# nes_mini.net
KiCad netlist of a schematic drawn in EAGLE
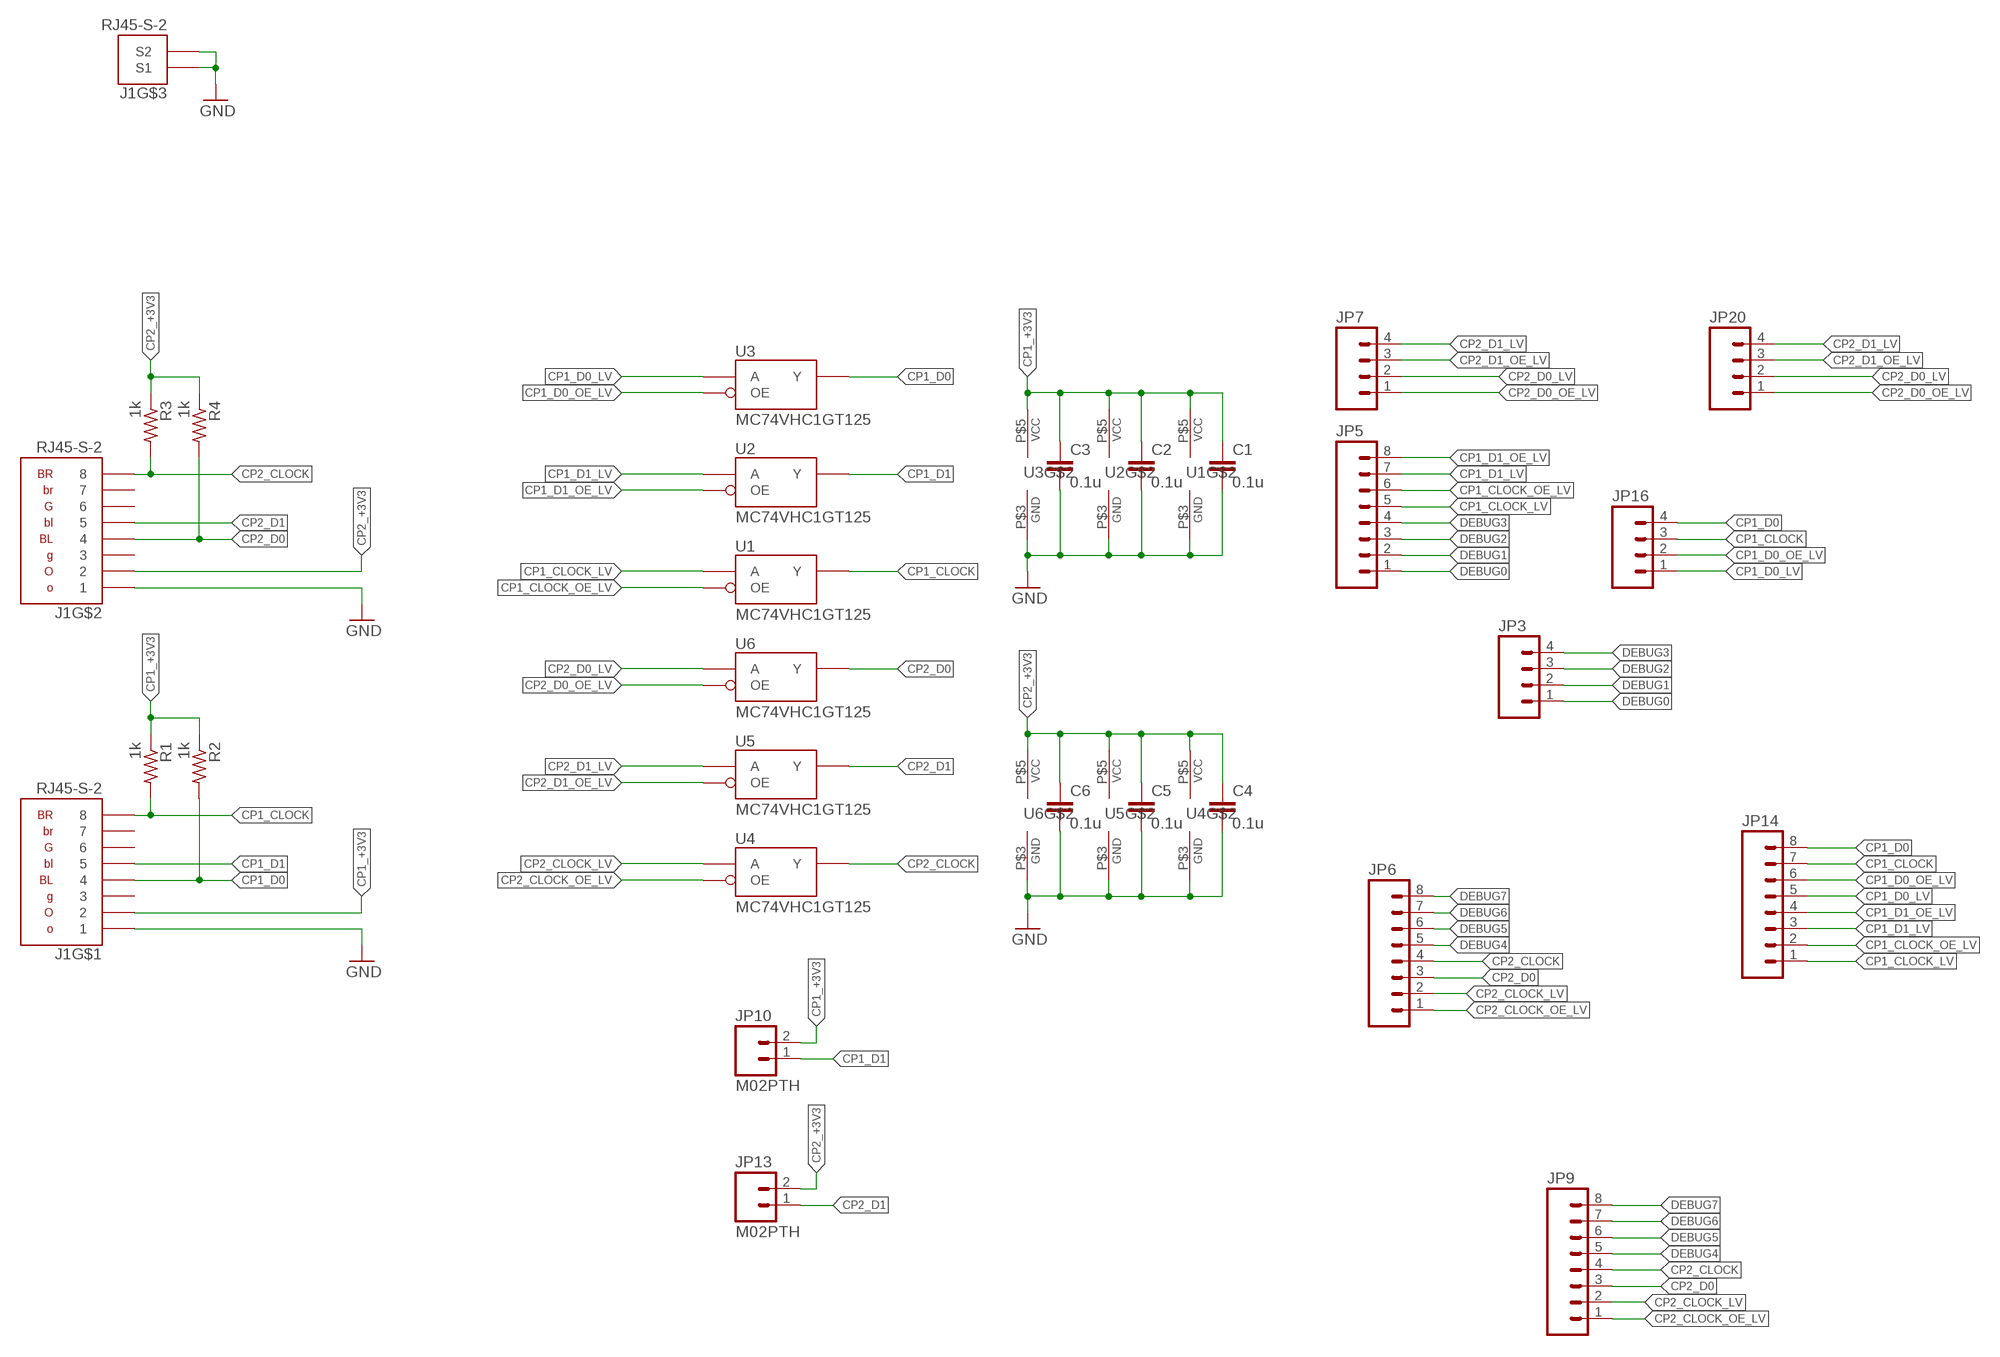
[diagram p0: schematic, sheet 1, part 1 of 2]
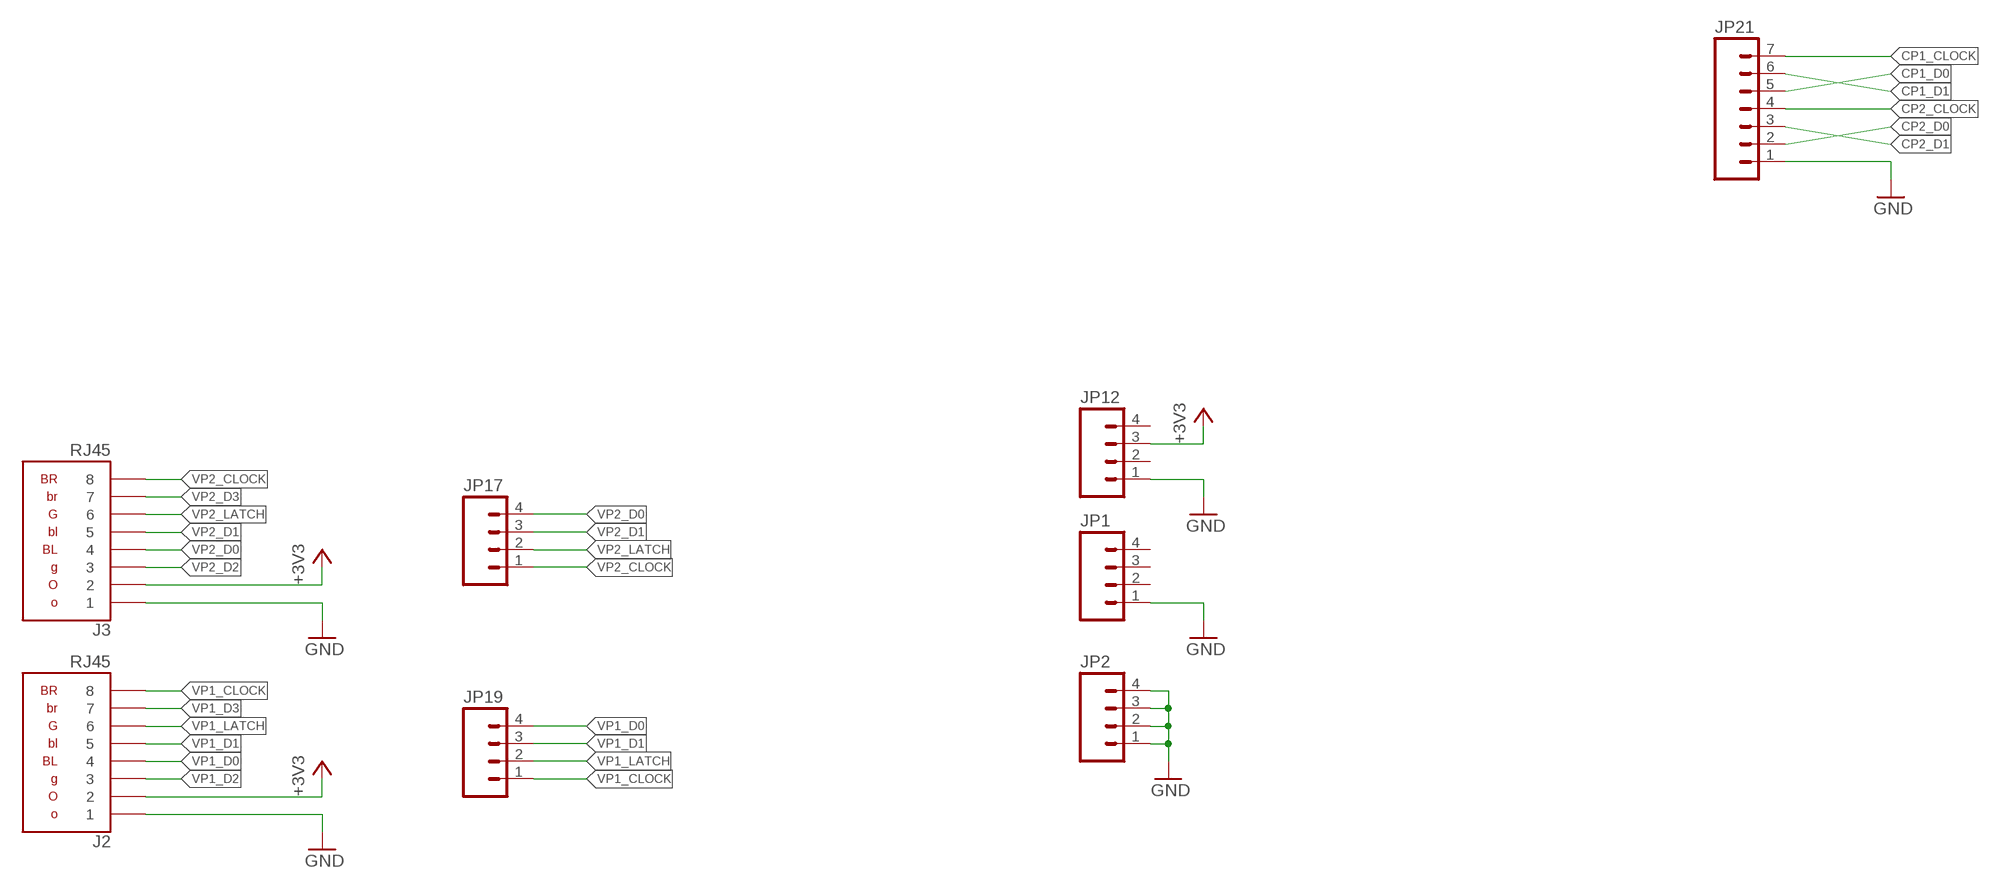
[diagram p1: schematic, sheet 1, part 2 of 2]

(export (version "E")
  (design (tool "Eeschema 10.0.6"))
  (components
    (comp (ref "C1")
      (value "0.1u")
      (footprint "eagle-import:C0603")
      (libsource (lib "eagle-import") (part "C-EUC0603"))
    )
    (comp (ref "C2")
      (value "0.1u")
      (footprint "eagle-import:C0603")
      (libsource (lib "eagle-import") (part "C-EUC0603"))
    )
    (comp (ref "C3")
      (value "0.1u")
      (footprint "eagle-import:C0603")
      (libsource (lib "eagle-import") (part "C-EUC0603"))
    )
    (comp (ref "C4")
      (value "0.1u")
      (footprint "eagle-import:C0603")
      (libsource (lib "eagle-import") (part "C-EUC0603"))
    )
    (comp (ref "C5")
      (value "0.1u")
      (footprint "eagle-import:C0603")
      (libsource (lib "eagle-import") (part "C-EUC0603"))
    )
    (comp (ref "C6")
      (value "0.1u")
      (footprint "eagle-import:C0603")
      (libsource (lib "eagle-import") (part "C-EUC0603"))
    )
    (comp (ref "J1")
      (value "RJ45-S-2")
      (footprint "eagle-import:RJ45-S-2")
      (libsource (lib "eagle-import") (part "RJ45-S-2"))
    )
    (comp (ref "J2")
      (value "RJ45")
      (footprint "eagle-import:RJ45")
      (libsource (lib "eagle-import") (part "RJ45"))
    )
    (comp (ref "J3")
      (value "RJ45")
      (footprint "eagle-import:RJ45")
      (libsource (lib "eagle-import") (part "RJ45"))
    )
    (comp (ref "JP1")
      (value "M04PTH")
      (footprint "eagle-import:1X04")
      (libsource (lib "eagle-import") (part "M04PTH"))
    )
    (comp (ref "JP2")
      (value "M04PTH")
      (footprint "eagle-import:1X04")
      (libsource (lib "eagle-import") (part "M04PTH"))
    )
    (comp (ref "JP3")
      (value "M04PTH")
      (footprint "eagle-import:1X04")
      (libsource (lib "eagle-import") (part "M04PTH"))
    )
    (comp (ref "JP5")
      (value "M081X08")
      (footprint "eagle-import:1X08")
      (libsource (lib "eagle-import") (part "M081X08"))
    )
    (comp (ref "JP6")
      (value "M081X08")
      (footprint "eagle-import:1X08")
      (libsource (lib "eagle-import") (part "M081X08"))
    )
    (comp (ref "JP7")
      (value "M04PTH")
      (footprint "eagle-import:1X04")
      (libsource (lib "eagle-import") (part "M04PTH"))
    )
    (comp (ref "JP9")
      (value "M081X08")
      (footprint "eagle-import:1X08")
      (libsource (lib "eagle-import") (part "M081X08"))
    )
    (comp (ref "JP10")
      (value "M02PTH")
      (footprint "eagle-import:1X02")
      (libsource (lib "eagle-import") (part "M02PTH"))
    )
    (comp (ref "JP12")
      (value "M04PTH")
      (footprint "eagle-import:1X04")
      (libsource (lib "eagle-import") (part "M04PTH"))
    )
    (comp (ref "JP13")
      (value "M02PTH")
      (footprint "eagle-import:1X02")
      (libsource (lib "eagle-import") (part "M02PTH"))
    )
    (comp (ref "JP14")
      (value "M081X08")
      (footprint "eagle-import:1X08")
      (libsource (lib "eagle-import") (part "M081X08"))
    )
    (comp (ref "JP16")
      (value "M04PTH")
      (footprint "eagle-import:1X04")
      (libsource (lib "eagle-import") (part "M04PTH"))
    )
    (comp (ref "JP17")
      (value "M04PTH")
      (footprint "eagle-import:1X04")
      (libsource (lib "eagle-import") (part "M04PTH"))
    )
    (comp (ref "JP19")
      (value "M04PTH")
      (footprint "eagle-import:1X04")
      (libsource (lib "eagle-import") (part "M04PTH"))
    )
    (comp (ref "JP20")
      (value "M04PTH")
      (footprint "eagle-import:1X04")
      (libsource (lib "eagle-import") (part "M04PTH"))
    )
    (comp (ref "JP21")
      (value "M07")
      (footprint "eagle-import:1X07")
      (libsource (lib "eagle-import") (part "M07"))
    )
    (comp (ref "R1")
      (value "1k")
      (footprint "eagle-import:0207_2V")
      (libsource (lib "eagle-import") (part "R-US_0207/2V"))
    )
    (comp (ref "R2")
      (value "1k")
      (footprint "eagle-import:0207_2V")
      (libsource (lib "eagle-import") (part "R-US_0207/2V"))
    )
    (comp (ref "R3")
      (value "1k")
      (footprint "eagle-import:0207_2V")
      (libsource (lib "eagle-import") (part "R-US_0207/2V"))
    )
    (comp (ref "R4")
      (value "1k")
      (footprint "eagle-import:0207_2V")
      (libsource (lib "eagle-import") (part "R-US_0207/2V"))
    )
    (comp (ref "U1")
      (value "MC74VHC1GT125")
      (footprint "eagle-import:TSOP-5")
      (libsource (lib "eagle-import") (part "MC74VHC1GT125"))
    )
    (comp (ref "U2")
      (value "MC74VHC1GT125")
      (footprint "eagle-import:TSOP-5")
      (libsource (lib "eagle-import") (part "MC74VHC1GT125"))
    )
    (comp (ref "U3")
      (value "MC74VHC1GT125")
      (footprint "eagle-import:TSOP-5")
      (libsource (lib "eagle-import") (part "MC74VHC1GT125"))
    )
    (comp (ref "U4")
      (value "MC74VHC1GT125")
      (footprint "eagle-import:TSOP-5")
      (libsource (lib "eagle-import") (part "MC74VHC1GT125"))
    )
    (comp (ref "U5")
      (value "MC74VHC1GT125")
      (footprint "eagle-import:TSOP-5")
      (libsource (lib "eagle-import") (part "MC74VHC1GT125"))
    )
    (comp (ref "U6")
      (value "MC74VHC1GT125")
      (footprint "eagle-import:TSOP-5")
      (libsource (lib "eagle-import") (part "MC74VHC1GT125"))
    )
  )
  (nets
    (net (code "1") (name "+3V3") (class "Default")
      (node (ref "J2") (pin "2") (pinfunction "2_2") (pintype "bidirectional"))
      (node (ref "J3") (pin "2") (pinfunction "2_2") (pintype "bidirectional"))
      (node (ref "JP12") (pin "3") (pinfunction "3_3") (pintype "passive"))
    )
    (net (code "2") (name "CP1_+3V3") (class "Default")
      (node (ref "C1") (pin "1") (pinfunction "1_1") (pintype "passive"))
      (node (ref "C2") (pin "1") (pinfunction "1_1") (pintype "passive"))
      (node (ref "C3") (pin "1") (pinfunction "1_1") (pintype "passive"))
      (node (ref "J1") (pin "1-2") (pinfunction "2_1-2") (pintype "bidirectional"))
      (node (ref "JP10") (pin "2") (pinfunction "2_2") (pintype "passive"))
      (node (ref "R1") (pin "1") (pinfunction "1_1") (pintype "passive"))
      (node (ref "R2") (pin "1") (pinfunction "1_1") (pintype "passive"))
      (node (ref "U1") (pin "P$5") (pinfunction "VCC_P$5") (pintype "power_in"))
      (node (ref "U2") (pin "P$5") (pinfunction "VCC_P$5") (pintype "power_in"))
      (node (ref "U3") (pin "P$5") (pinfunction "VCC_P$5") (pintype "power_in"))
    )
    (net (code "3") (name "CP1_CLOCK") (class "Default")
      (node (ref "J1") (pin "1-8") (pinfunction "8_1-8") (pintype "bidirectional"))
      (node (ref "JP14") (pin "7") (pinfunction "7_7") (pintype "passive"))
      (node (ref "JP16") (pin "3") (pinfunction "3_3") (pintype "passive"))
      (node (ref "JP21") (pin "7") (pinfunction "7_7") (pintype "passive"))
      (node (ref "R1") (pin "2") (pinfunction "2_2") (pintype "passive"))
      (node (ref "U1") (pin "P$4") (pinfunction "Y_P$4") (pintype "bidirectional"))
    )
    (net (code "4") (name "CP1_CLOCK_LV") (class "Default")
      (node (ref "JP14") (pin "1") (pinfunction "1_1") (pintype "passive"))
      (node (ref "JP5") (pin "5") (pinfunction "5_5") (pintype "passive"))
      (node (ref "U1") (pin "P$2") (pinfunction "A_P$2") (pintype "bidirectional"))
    )
    (net (code "5") (name "CP1_CLOCK_OE_LV") (class "Default")
      (node (ref "JP14") (pin "2") (pinfunction "2_2") (pintype "passive"))
      (node (ref "JP5") (pin "6") (pinfunction "6_6") (pintype "passive"))
      (node (ref "U1") (pin "P$1") (pinfunction "OE_P$1") (pintype "bidirectional"))
    )
    (net (code "6") (name "CP1_D0") (class "Default")
      (node (ref "J1") (pin "1-4") (pinfunction "4_1-4") (pintype "bidirectional"))
      (node (ref "JP14") (pin "8") (pinfunction "8_8") (pintype "passive"))
      (node (ref "JP16") (pin "4") (pinfunction "4_4") (pintype "passive"))
      (node (ref "JP21") (pin "5") (pinfunction "5_5") (pintype "passive"))
      (node (ref "R2") (pin "2") (pinfunction "2_2") (pintype "passive"))
      (node (ref "U3") (pin "P$4") (pinfunction "Y_P$4") (pintype "bidirectional"))
    )
    (net (code "7") (name "CP1_D0_LV") (class "Default")
      (node (ref "JP14") (pin "5") (pinfunction "5_5") (pintype "passive"))
      (node (ref "JP16") (pin "1") (pinfunction "1_1") (pintype "passive"))
      (node (ref "U3") (pin "P$2") (pinfunction "A_P$2") (pintype "bidirectional"))
    )
    (net (code "8") (name "CP1_D0_OE_LV") (class "Default")
      (node (ref "JP14") (pin "6") (pinfunction "6_6") (pintype "passive"))
      (node (ref "JP16") (pin "2") (pinfunction "2_2") (pintype "passive"))
      (node (ref "U3") (pin "P$1") (pinfunction "OE_P$1") (pintype "bidirectional"))
    )
    (net (code "9") (name "CP1_D1") (class "Default")
      (node (ref "J1") (pin "1-5") (pinfunction "5_1-5") (pintype "bidirectional"))
      (node (ref "JP10") (pin "1") (pinfunction "1_1") (pintype "passive"))
      (node (ref "JP21") (pin "6") (pinfunction "6_6") (pintype "passive"))
      (node (ref "U2") (pin "P$4") (pinfunction "Y_P$4") (pintype "bidirectional"))
    )
    (net (code "10") (name "CP1_D1_LV") (class "Default")
      (node (ref "JP14") (pin "3") (pinfunction "3_3") (pintype "passive"))
      (node (ref "JP5") (pin "7") (pinfunction "7_7") (pintype "passive"))
      (node (ref "U2") (pin "P$2") (pinfunction "A_P$2") (pintype "bidirectional"))
    )
    (net (code "11") (name "CP1_D1_OE_LV") (class "Default")
      (node (ref "JP14") (pin "4") (pinfunction "4_4") (pintype "passive"))
      (node (ref "JP5") (pin "8") (pinfunction "8_8") (pintype "passive"))
      (node (ref "U2") (pin "P$1") (pinfunction "OE_P$1") (pintype "bidirectional"))
    )
    (net (code "12") (name "CP2_+3V3") (class "Default")
      (node (ref "C4") (pin "1") (pinfunction "1_1") (pintype "passive"))
      (node (ref "C5") (pin "1") (pinfunction "1_1") (pintype "passive"))
      (node (ref "C6") (pin "1") (pinfunction "1_1") (pintype "passive"))
      (node (ref "J1") (pin "2-2") (pinfunction "2_2-2") (pintype "bidirectional"))
      (node (ref "JP13") (pin "2") (pinfunction "2_2") (pintype "passive"))
      (node (ref "R3") (pin "1") (pinfunction "1_1") (pintype "passive"))
      (node (ref "R4") (pin "1") (pinfunction "1_1") (pintype "passive"))
      (node (ref "U4") (pin "P$5") (pinfunction "VCC_P$5") (pintype "power_in"))
      (node (ref "U5") (pin "P$5") (pinfunction "VCC_P$5") (pintype "power_in"))
      (node (ref "U6") (pin "P$5") (pinfunction "VCC_P$5") (pintype "power_in"))
    )
    (net (code "13") (name "CP2_CLOCK") (class "Default")
      (node (ref "J1") (pin "2-8") (pinfunction "8_2-8") (pintype "bidirectional"))
      (node (ref "JP21") (pin "4") (pinfunction "4_4") (pintype "passive"))
      (node (ref "JP6") (pin "4") (pinfunction "4_4") (pintype "passive"))
      (node (ref "JP9") (pin "4") (pinfunction "4_4") (pintype "passive"))
      (node (ref "R3") (pin "2") (pinfunction "2_2") (pintype "passive"))
      (node (ref "U4") (pin "P$4") (pinfunction "Y_P$4") (pintype "bidirectional"))
    )
    (net (code "14") (name "CP2_CLOCK_LV") (class "Default")
      (node (ref "JP6") (pin "2") (pinfunction "2_2") (pintype "passive"))
      (node (ref "JP9") (pin "2") (pinfunction "2_2") (pintype "passive"))
      (node (ref "U4") (pin "P$2") (pinfunction "A_P$2") (pintype "bidirectional"))
    )
    (net (code "15") (name "CP2_CLOCK_OE_LV") (class "Default")
      (node (ref "JP6") (pin "1") (pinfunction "1_1") (pintype "passive"))
      (node (ref "JP9") (pin "1") (pinfunction "1_1") (pintype "passive"))
      (node (ref "U4") (pin "P$1") (pinfunction "OE_P$1") (pintype "bidirectional"))
    )
    (net (code "16") (name "CP2_D0") (class "Default")
      (node (ref "J1") (pin "2-4") (pinfunction "4_2-4") (pintype "bidirectional"))
      (node (ref "JP21") (pin "2") (pinfunction "2_2") (pintype "passive"))
      (node (ref "JP6") (pin "3") (pinfunction "3_3") (pintype "passive"))
      (node (ref "JP9") (pin "3") (pinfunction "3_3") (pintype "passive"))
      (node (ref "R4") (pin "2") (pinfunction "2_2") (pintype "passive"))
      (node (ref "U6") (pin "P$4") (pinfunction "Y_P$4") (pintype "bidirectional"))
    )
    (net (code "17") (name "CP2_D0_LV") (class "Default")
      (node (ref "JP20") (pin "2") (pinfunction "2_2") (pintype "passive"))
      (node (ref "JP7") (pin "2") (pinfunction "2_2") (pintype "passive"))
      (node (ref "U6") (pin "P$2") (pinfunction "A_P$2") (pintype "bidirectional"))
    )
    (net (code "18") (name "CP2_D0_OE_LV") (class "Default")
      (node (ref "JP20") (pin "1") (pinfunction "1_1") (pintype "passive"))
      (node (ref "JP7") (pin "1") (pinfunction "1_1") (pintype "passive"))
      (node (ref "U6") (pin "P$1") (pinfunction "OE_P$1") (pintype "bidirectional"))
    )
    (net (code "19") (name "CP2_D1") (class "Default")
      (node (ref "J1") (pin "2-5") (pinfunction "5_2-5") (pintype "bidirectional"))
      (node (ref "JP13") (pin "1") (pinfunction "1_1") (pintype "passive"))
      (node (ref "JP21") (pin "3") (pinfunction "3_3") (pintype "passive"))
      (node (ref "U5") (pin "P$4") (pinfunction "Y_P$4") (pintype "bidirectional"))
    )
    (net (code "20") (name "CP2_D1_LV") (class "Default")
      (node (ref "JP20") (pin "4") (pinfunction "4_4") (pintype "passive"))
      (node (ref "JP7") (pin "4") (pinfunction "4_4") (pintype "passive"))
      (node (ref "U5") (pin "P$2") (pinfunction "A_P$2") (pintype "bidirectional"))
    )
    (net (code "21") (name "CP2_D1_OE_LV") (class "Default")
      (node (ref "JP20") (pin "3") (pinfunction "3_3") (pintype "passive"))
      (node (ref "JP7") (pin "3") (pinfunction "3_3") (pintype "passive"))
      (node (ref "U5") (pin "P$1") (pinfunction "OE_P$1") (pintype "bidirectional"))
    )
    (net (code "22") (name "DEBUG0") (class "Default")
      (node (ref "JP3") (pin "1") (pinfunction "1_1") (pintype "passive"))
      (node (ref "JP5") (pin "1") (pinfunction "1_1") (pintype "passive"))
    )
    (net (code "23") (name "DEBUG1") (class "Default")
      (node (ref "JP3") (pin "2") (pinfunction "2_2") (pintype "passive"))
      (node (ref "JP5") (pin "2") (pinfunction "2_2") (pintype "passive"))
    )
    (net (code "24") (name "DEBUG2") (class "Default")
      (node (ref "JP3") (pin "3") (pinfunction "3_3") (pintype "passive"))
      (node (ref "JP5") (pin "3") (pinfunction "3_3") (pintype "passive"))
    )
    (net (code "25") (name "DEBUG3") (class "Default")
      (node (ref "JP3") (pin "4") (pinfunction "4_4") (pintype "passive"))
      (node (ref "JP5") (pin "4") (pinfunction "4_4") (pintype "passive"))
    )
    (net (code "26") (name "DEBUG4") (class "Default")
      (node (ref "JP6") (pin "5") (pinfunction "5_5") (pintype "passive"))
      (node (ref "JP9") (pin "5") (pinfunction "5_5") (pintype "passive"))
    )
    (net (code "27") (name "DEBUG5") (class "Default")
      (node (ref "JP6") (pin "6") (pinfunction "6_6") (pintype "passive"))
      (node (ref "JP9") (pin "6") (pinfunction "6_6") (pintype "passive"))
    )
    (net (code "28") (name "DEBUG6") (class "Default")
      (node (ref "JP6") (pin "7") (pinfunction "7_7") (pintype "passive"))
      (node (ref "JP9") (pin "7") (pinfunction "7_7") (pintype "passive"))
    )
    (net (code "29") (name "DEBUG7") (class "Default")
      (node (ref "JP6") (pin "8") (pinfunction "8_8") (pintype "passive"))
      (node (ref "JP9") (pin "8") (pinfunction "8_8") (pintype "passive"))
    )
    (net (code "30") (name "GND") (class "Default")
      (node (ref "C1") (pin "2") (pinfunction "2_2") (pintype "passive"))
      (node (ref "C2") (pin "2") (pinfunction "2_2") (pintype "passive"))
      (node (ref "C3") (pin "2") (pinfunction "2_2") (pintype "passive"))
      (node (ref "C4") (pin "2") (pinfunction "2_2") (pintype "passive"))
      (node (ref "C5") (pin "2") (pinfunction "2_2") (pintype "passive"))
      (node (ref "C6") (pin "2") (pinfunction "2_2") (pintype "passive"))
      (node (ref "J1") (pin "1-1") (pinfunction "1_1-1") (pintype "bidirectional"))
      (node (ref "J1") (pin "2-1") (pinfunction "1_2-1") (pintype "bidirectional"))
      (node (ref "J1") (pin "S1") (pinfunction "S1_S1") (pintype "bidirectional"))
      (node (ref "J1") (pin "S2") (pinfunction "S2_S2") (pintype "bidirectional"))
      (node (ref "J2") (pin "1") (pinfunction "1_1") (pintype "bidirectional"))
      (node (ref "J3") (pin "1") (pinfunction "1_1") (pintype "bidirectional"))
      (node (ref "JP1") (pin "1") (pinfunction "1_1") (pintype "passive"))
      (node (ref "JP12") (pin "1") (pinfunction "1_1") (pintype "passive"))
      (node (ref "JP2") (pin "1") (pinfunction "1_1") (pintype "passive"))
      (node (ref "JP2") (pin "2") (pinfunction "2_2") (pintype "passive"))
      (node (ref "JP2") (pin "3") (pinfunction "3_3") (pintype "passive"))
      (node (ref "JP2") (pin "4") (pinfunction "4_4") (pintype "passive"))
      (node (ref "JP21") (pin "1") (pinfunction "1_1") (pintype "passive"))
      (node (ref "U1") (pin "P$3") (pinfunction "GND_P$3") (pintype "power_in"))
      (node (ref "U2") (pin "P$3") (pinfunction "GND_P$3") (pintype "power_in"))
      (node (ref "U3") (pin "P$3") (pinfunction "GND_P$3") (pintype "power_in"))
      (node (ref "U4") (pin "P$3") (pinfunction "GND_P$3") (pintype "power_in"))
      (node (ref "U5") (pin "P$3") (pinfunction "GND_P$3") (pintype "power_in"))
      (node (ref "U6") (pin "P$3") (pinfunction "GND_P$3") (pintype "power_in"))
    )
    (net (code "31") (name "VP1_CLOCK") (class "Default")
      (node (ref "J2") (pin "8") (pinfunction "8_8") (pintype "bidirectional"))
      (node (ref "JP19") (pin "1") (pinfunction "1_1") (pintype "passive"))
    )
    (net (code "32") (name "VP1_D0") (class "Default")
      (node (ref "J2") (pin "4") (pinfunction "4_4") (pintype "bidirectional"))
      (node (ref "JP19") (pin "4") (pinfunction "4_4") (pintype "passive"))
    )
    (net (code "33") (name "VP1_D1") (class "Default")
      (node (ref "J2") (pin "5") (pinfunction "5_5") (pintype "bidirectional"))
      (node (ref "JP19") (pin "3") (pinfunction "3_3") (pintype "passive"))
    )
    (net (code "34") (name "VP1_D2") (class "Default")
      (node (ref "J2") (pin "3") (pinfunction "3_3") (pintype "bidirectional"))
    )
    (net (code "35") (name "VP1_D3") (class "Default")
      (node (ref "J2") (pin "7") (pinfunction "7_7") (pintype "bidirectional"))
    )
    (net (code "36") (name "VP1_LATCH") (class "Default")
      (node (ref "J2") (pin "6") (pinfunction "6_6") (pintype "bidirectional"))
      (node (ref "JP19") (pin "2") (pinfunction "2_2") (pintype "passive"))
    )
    (net (code "37") (name "VP2_CLOCK") (class "Default")
      (node (ref "J3") (pin "8") (pinfunction "8_8") (pintype "bidirectional"))
      (node (ref "JP17") (pin "1") (pinfunction "1_1") (pintype "passive"))
    )
    (net (code "38") (name "VP2_D0") (class "Default")
      (node (ref "J3") (pin "4") (pinfunction "4_4") (pintype "bidirectional"))
      (node (ref "JP17") (pin "4") (pinfunction "4_4") (pintype "passive"))
    )
    (net (code "39") (name "VP2_D1") (class "Default")
      (node (ref "J3") (pin "5") (pinfunction "5_5") (pintype "bidirectional"))
      (node (ref "JP17") (pin "3") (pinfunction "3_3") (pintype "passive"))
    )
    (net (code "40") (name "VP2_D2") (class "Default")
      (node (ref "J3") (pin "3") (pinfunction "3_3") (pintype "bidirectional"))
    )
    (net (code "41") (name "VP2_D3") (class "Default")
      (node (ref "J3") (pin "7") (pinfunction "7_7") (pintype "bidirectional"))
    )
    (net (code "42") (name "VP2_LATCH") (class "Default")
      (node (ref "J3") (pin "6") (pinfunction "6_6") (pintype "bidirectional"))
      (node (ref "JP17") (pin "2") (pinfunction "2_2") (pintype "passive"))
    )
    (net (code "43") (name "unconnected-(J1A-3-Pad1-3)") (class "Default")
      (node (ref "J1") (pin "1-3") (pinfunction "3_1-3") (pintype "bidirectional"))
    )
    (net (code "44") (name "unconnected-(J1A-6-Pad1-6)") (class "Default")
      (node (ref "J1") (pin "1-6") (pinfunction "6_1-6") (pintype "bidirectional"))
    )
    (net (code "45") (name "unconnected-(J1A-7-Pad1-7)") (class "Default")
      (node (ref "J1") (pin "1-7") (pinfunction "7_1-7") (pintype "bidirectional"))
    )
    (net (code "46") (name "unconnected-(J1B-3-Pad2-3)") (class "Default")
      (node (ref "J1") (pin "2-3") (pinfunction "3_2-3") (pintype "bidirectional"))
    )
    (net (code "47") (name "unconnected-(J1B-6-Pad2-6)") (class "Default")
      (node (ref "J1") (pin "2-6") (pinfunction "6_2-6") (pintype "bidirectional"))
    )
    (net (code "48") (name "unconnected-(J1B-7-Pad2-7)") (class "Default")
      (node (ref "J1") (pin "2-7") (pinfunction "7_2-7") (pintype "bidirectional"))
    )
    (net (code "49") (name "unconnected-(JP1-Pad2)") (class "Default")
      (node (ref "JP1") (pin "2") (pinfunction "2_2") (pintype "passive"))
    )
    (net (code "50") (name "unconnected-(JP1-Pad3)") (class "Default")
      (node (ref "JP1") (pin "3") (pinfunction "3_3") (pintype "passive"))
    )
    (net (code "51") (name "unconnected-(JP1-Pad4)") (class "Default")
      (node (ref "JP1") (pin "4") (pinfunction "4_4") (pintype "passive"))
    )
    (net (code "52") (name "unconnected-(JP12-Pad2)") (class "Default")
      (node (ref "JP12") (pin "2") (pinfunction "2_2") (pintype "passive"))
    )
    (net (code "53") (name "unconnected-(JP12-Pad4)") (class "Default")
      (node (ref "JP12") (pin "4") (pinfunction "4_4") (pintype "passive"))
    )
  )
)
